# QCopterMV-Expand2_Sch.net
KiCad netlist of a schematic drawn in Altium Designer
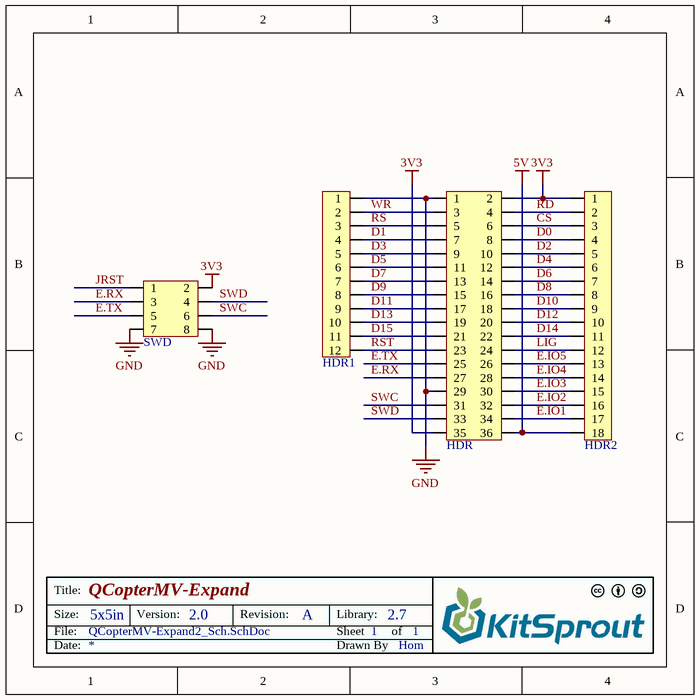
[diagram p0: QCopterMV-Expand2_Sch.SchDoc]

(export (version "E")
  (design (tool "Eeschema 10.0.6"))
  (components
    (comp (ref "HDR")
      (value "HDR2x18_1.27")
      (footprint "PCB_ConnectorHDR:HDR2x18_1.27_180")
      (description "Header")
      (libsource (lib "SCH_ConnectorHDR") (part "HDR2x18_1.27"))
    )
    (comp (ref "HDR1")
      (value "HDR1x12_2.54T")
      (footprint "PCB_ConnectorHDR:HDR1X12_2.54_180")
      (description "Header")
      (libsource (lib "SCH_ConnectorHDR") (part "HDR1x12_2.54T"))
    )
    (comp (ref "HDR2")
      (value "HDR1x18_2.54")
      (footprint "PCB_ConnectorHDR:HDR1X18_2.54_180")
      (description "Header")
      (libsource (lib "SCH_ConnectorHDR") (part "HDR1x18_2.54"))
    )
    (comp (ref "SWD")
      (value "HDR2x4_2.54")
      (footprint "PCB_ConnectorHDR:HDR2X4_2.54_180HF")
      (description "Header")
      (libsource (lib "SCH_ConnectorHDR") (part "HDR2x4_2.54"))
    )
  )
  (nets
    (net (code "1") (name "/CS") (class "Default")
      (node (ref "HDR") (pin "6") (pinfunction "6_6") (pintype "passive"))
      (node (ref "HDR2") (pin "3") (pinfunction "3_3") (pintype "passive"))
    )
    (net (code "2") (name "/D0") (class "Default")
      (node (ref "HDR") (pin "8") (pinfunction "8_8") (pintype "passive"))
      (node (ref "HDR2") (pin "4") (pinfunction "4_4") (pintype "passive"))
    )
    (net (code "3") (name "/D1") (class "Default")
      (node (ref "HDR") (pin "7") (pinfunction "7_7") (pintype "passive"))
      (node (ref "HDR1") (pin "4") (pinfunction "4_4") (pintype "passive"))
    )
    (net (code "4") (name "/D2") (class "Default")
      (node (ref "HDR") (pin "10") (pinfunction "10_10") (pintype "passive"))
      (node (ref "HDR2") (pin "5") (pinfunction "5_5") (pintype "passive"))
    )
    (net (code "5") (name "/D3") (class "Default")
      (node (ref "HDR") (pin "9") (pinfunction "9_9") (pintype "passive"))
      (node (ref "HDR1") (pin "5") (pinfunction "5_5") (pintype "passive"))
    )
    (net (code "6") (name "/D4") (class "Default")
      (node (ref "HDR") (pin "12") (pinfunction "12_12") (pintype "passive"))
      (node (ref "HDR2") (pin "6") (pinfunction "6_6") (pintype "passive"))
    )
    (net (code "7") (name "/D5") (class "Default")
      (node (ref "HDR") (pin "11") (pinfunction "11_11") (pintype "passive"))
      (node (ref "HDR1") (pin "6") (pinfunction "6_6") (pintype "passive"))
    )
    (net (code "8") (name "/D6") (class "Default")
      (node (ref "HDR") (pin "14") (pinfunction "14_14") (pintype "passive"))
      (node (ref "HDR2") (pin "7") (pinfunction "7_7") (pintype "passive"))
    )
    (net (code "9") (name "/D7") (class "Default")
      (node (ref "HDR") (pin "13") (pinfunction "13_13") (pintype "passive"))
      (node (ref "HDR1") (pin "7") (pinfunction "7_7") (pintype "passive"))
    )
    (net (code "10") (name "/D8") (class "Default")
      (node (ref "HDR") (pin "16") (pinfunction "16_16") (pintype "passive"))
      (node (ref "HDR2") (pin "8") (pinfunction "8_8") (pintype "passive"))
    )
    (net (code "11") (name "/D9") (class "Default")
      (node (ref "HDR") (pin "15") (pinfunction "15_15") (pintype "passive"))
      (node (ref "HDR1") (pin "8") (pinfunction "8_8") (pintype "passive"))
    )
    (net (code "12") (name "/D10") (class "Default")
      (node (ref "HDR") (pin "18") (pinfunction "18_18") (pintype "passive"))
      (node (ref "HDR2") (pin "9") (pinfunction "9_9") (pintype "passive"))
    )
    (net (code "13") (name "/D11") (class "Default")
      (node (ref "HDR") (pin "17") (pinfunction "17_17") (pintype "passive"))
      (node (ref "HDR1") (pin "9") (pinfunction "9_9") (pintype "passive"))
    )
    (net (code "14") (name "/D12") (class "Default")
      (node (ref "HDR") (pin "20") (pinfunction "20_20") (pintype "passive"))
      (node (ref "HDR2") (pin "10") (pinfunction "10_10") (pintype "passive"))
    )
    (net (code "15") (name "/D13") (class "Default")
      (node (ref "HDR") (pin "19") (pinfunction "19_19") (pintype "passive"))
      (node (ref "HDR1") (pin "10") (pinfunction "10_10") (pintype "passive"))
    )
    (net (code "16") (name "/D14") (class "Default")
      (node (ref "HDR") (pin "22") (pinfunction "22_22") (pintype "passive"))
      (node (ref "HDR2") (pin "11") (pinfunction "11_11") (pintype "passive"))
    )
    (net (code "17") (name "/D15") (class "Default")
      (node (ref "HDR") (pin "21") (pinfunction "21_21") (pintype "passive"))
      (node (ref "HDR1") (pin "11") (pinfunction "11_11") (pintype "passive"))
    )
    (net (code "18") (name "/E.IO1") (class "Default")
      (node (ref "HDR") (pin "34") (pinfunction "34_34") (pintype "passive"))
      (node (ref "HDR2") (pin "17") (pinfunction "17_17") (pintype "passive"))
    )
    (net (code "19") (name "/E.IO2") (class "Default")
      (node (ref "HDR") (pin "32") (pinfunction "32_32") (pintype "passive"))
      (node (ref "HDR2") (pin "16") (pinfunction "16_16") (pintype "passive"))
    )
    (net (code "20") (name "/E.IO3") (class "Default")
      (node (ref "HDR") (pin "30") (pinfunction "30_30") (pintype "passive"))
      (node (ref "HDR2") (pin "15") (pinfunction "15_15") (pintype "passive"))
    )
    (net (code "21") (name "/E.IO4") (class "Default")
      (node (ref "HDR") (pin "28") (pinfunction "28_28") (pintype "passive"))
      (node (ref "HDR2") (pin "14") (pinfunction "14_14") (pintype "passive"))
    )
    (net (code "22") (name "/E.IO5") (class "Default")
      (node (ref "HDR") (pin "26") (pinfunction "26_26") (pintype "passive"))
      (node (ref "HDR2") (pin "13") (pinfunction "13_13") (pintype "passive"))
    )
    (net (code "23") (name "/E.RX") (class "Default")
      (node (ref "HDR") (pin "27") (pinfunction "27_27") (pintype "passive"))
      (node (ref "SWD") (pin "3") (pinfunction "3_3") (pintype "passive"))
    )
    (net (code "24") (name "/E.TX") (class "Default")
      (node (ref "HDR") (pin "25") (pinfunction "25_25") (pintype "passive"))
      (node (ref "SWD") (pin "5") (pinfunction "5_5") (pintype "passive"))
    )
    (net (code "25") (name "/JRST") (class "Default")
      (node (ref "SWD") (pin "1") (pinfunction "1_1") (pintype "passive"))
    )
    (net (code "26") (name "/LIG") (class "Default")
      (node (ref "HDR") (pin "24") (pinfunction "24_24") (pintype "passive"))
      (node (ref "HDR2") (pin "12") (pinfunction "12_12") (pintype "passive"))
    )
    (net (code "27") (name "/RD") (class "Default")
      (node (ref "HDR") (pin "4") (pinfunction "4_4") (pintype "passive"))
      (node (ref "HDR2") (pin "2") (pinfunction "2_2") (pintype "passive"))
    )
    (net (code "28") (name "/RS") (class "Default")
      (node (ref "HDR") (pin "5") (pinfunction "5_5") (pintype "passive"))
      (node (ref "HDR1") (pin "3") (pinfunction "3_3") (pintype "passive"))
    )
    (net (code "29") (name "/RST") (class "Default")
      (node (ref "HDR") (pin "23") (pinfunction "23_23") (pintype "passive"))
      (node (ref "HDR1") (pin "12") (pinfunction "12_12") (pintype "passive"))
    )
    (net (code "30") (name "/SWC") (class "Default")
      (node (ref "HDR") (pin "31") (pinfunction "31_31") (pintype "passive"))
      (node (ref "SWD") (pin "6") (pinfunction "6_6") (pintype "passive"))
    )
    (net (code "31") (name "/SWD") (class "Default")
      (node (ref "HDR") (pin "33") (pinfunction "33_33") (pintype "passive"))
      (node (ref "SWD") (pin "4") (pinfunction "4_4") (pintype "passive"))
    )
    (net (code "32") (name "/WR") (class "Default")
      (node (ref "HDR") (pin "3") (pinfunction "3_3") (pintype "passive"))
      (node (ref "HDR1") (pin "2") (pinfunction "2_2") (pintype "passive"))
    )
    (net (code "33") (name "3V3") (class "Default")
      (node (ref "HDR") (pin "2") (pinfunction "2_2") (pintype "passive"))
      (node (ref "HDR") (pin "35") (pinfunction "35_35") (pintype "passive"))
      (node (ref "HDR2") (pin "1") (pinfunction "1_1") (pintype "passive"))
      (node (ref "SWD") (pin "2") (pinfunction "2_2") (pintype "passive"))
    )
    (net (code "34") (name "5V") (class "Default")
      (node (ref "HDR") (pin "36") (pinfunction "36_36") (pintype "passive"))
      (node (ref "HDR2") (pin "18") (pinfunction "18_18") (pintype "passive"))
    )
    (net (code "35") (name "GND") (class "Default")
      (node (ref "HDR") (pin "1") (pinfunction "1_1") (pintype "passive"))
      (node (ref "HDR") (pin "29") (pinfunction "29_29") (pintype "passive"))
      (node (ref "HDR1") (pin "1") (pinfunction "1_1") (pintype "passive"))
      (node (ref "SWD") (pin "7") (pinfunction "7_7") (pintype "passive"))
      (node (ref "SWD") (pin "8") (pinfunction "8_8") (pintype "passive"))
    )
  )
)
